# StrobeV3.net
KiCad netlist of a schematic drawn in EAGLE
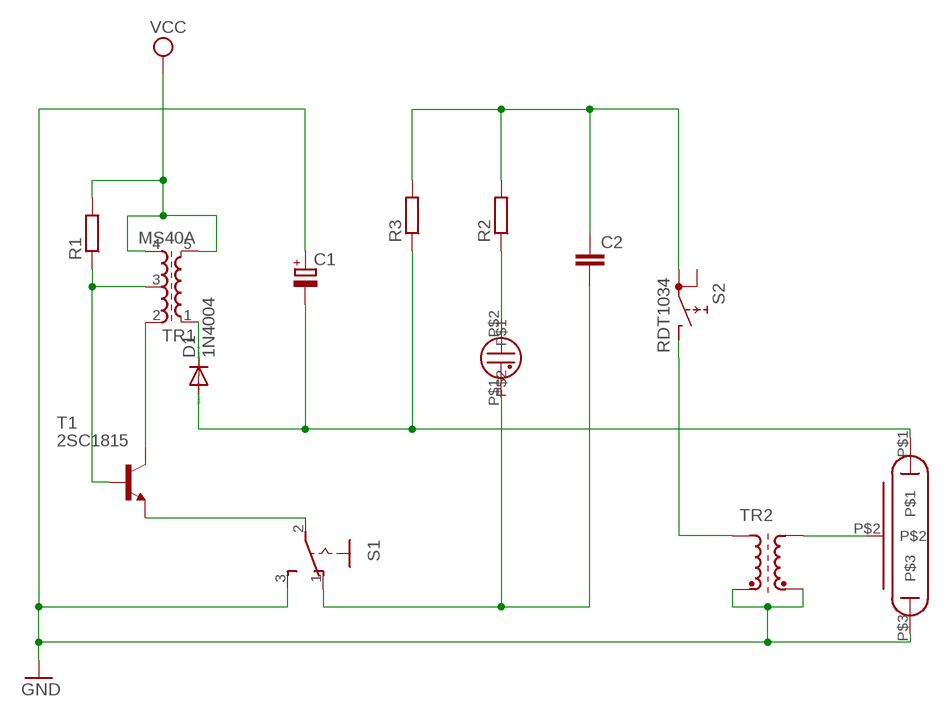
[diagram p0: schematic, sheet 1]

(export (version "E")
  (design (tool "Eeschema 10.0.6"))
  (components
    (comp (ref "C1")
      (value "CPOL-EU140CLH-0810")
      (footprint "eagle-import:140CLH-0810")
      (libsource (lib "eagle-import") (part "CPOL-EU140CLH-0810"))
    )
    (comp (ref "C2")
      (value "C-EU150-054X183")
      (footprint "eagle-import:C150-054X183")
      (libsource (lib "eagle-import") (part "C-EU150-054X183"))
    )
    (comp (ref "D1")
      (value "1N4004")
      (footprint "eagle-import:DO41-10")
      (libsource (lib "eagle-import") (part "1N4004"))
    )
    (comp (ref "R1")
      (value "R-EU_0204/2V")
      (footprint "eagle-import:0204V")
      (libsource (lib "eagle-import") (part "R-EU_0204/2V"))
    )
    (comp (ref "R2")
      (value "R-EU_0204/2V")
      (footprint "eagle-import:0204V")
      (libsource (lib "eagle-import") (part "R-EU_0204/2V"))
    )
    (comp (ref "R3")
      (value "R-EU_0204/2V")
      (footprint "eagle-import:0204V")
      (libsource (lib "eagle-import") (part "R-EU_0204/2V"))
    )
    (comp (ref "S1")
      (value "255SB")
      (footprint "eagle-import:255SB")
      (libsource (lib "eagle-import") (part "255SB"))
    )
    (comp (ref "S2")
      (value "RDT1034")
      (footprint "eagle-import:RDT1034")
      (libsource (lib "eagle-import") (part "RDT1034"))
    )
    (comp (ref "T1")
      (value "2SC1815")
      (footprint "eagle-import:TO92-ECB")
      (libsource (lib "eagle-import") (part "2SC1815"))
    )
    (comp (ref "TR1")
      (value "MS40A")
      (footprint "eagle-import:MS40")
      (libsource (lib "eagle-import") (part "MS40A"))
    )
    (comp (ref "TR2")
      (value "SM-T4")
      (footprint "eagle-import:SM-T4")
      (libsource (lib "eagle-import") (part "SM-T4"))
    )
    (comp (ref "U$1")
      (value "XENON")
      (footprint "eagle-import:XENON")
      (libsource (lib "eagle-import") (part "XENON"))
    )
    (comp (ref "U$2")
      (value "NEON")
      (footprint "eagle-import:NEON")
      (libsource (lib "eagle-import") (part "NEON"))
    )
  )
  (nets
    (net (code "1") (name "GND") (class "Default")
      (node (ref "C1") (pin "+") (pinfunction "+_+") (pintype "passive"))
      (node (ref "S1") (pin "3") (pinfunction "S_3") (pintype "passive"))
      (node (ref "TR2") (pin "2") (pinfunction "E1_2") (pintype "passive"))
      (node (ref "TR2") (pin "4") (pinfunction "E2_4") (pintype "passive"))
      (node (ref "U$1") (pin "P$3") (pinfunction "P$3_P$3") (pintype "bidirectional"))
    )
    (net (code "2") (name "Net-(C1-Pad-)") (class "Default")
      (node (ref "C1") (pin "-") (pinfunction "-_-") (pintype "passive"))
      (node (ref "D1") (pin "A") (pinfunction "A_A") (pintype "passive"))
      (node (ref "R3") (pin "1") (pinfunction "1_1") (pintype "passive"))
      (node (ref "U$1") (pin "P$1") (pinfunction "P$1_P$1") (pintype "bidirectional"))
    )
    (net (code "3") (name "Net-(C2-Pad1)") (class "Default")
      (node (ref "C2") (pin "1") (pinfunction "1_1") (pintype "passive"))
      (node (ref "R2") (pin "2") (pinfunction "2_2") (pintype "passive"))
      (node (ref "R3") (pin "2") (pinfunction "2_2") (pintype "passive"))
      (node (ref "S2") (pin "A1") (pinfunction "A1_A1") (pintype "passive"))
    )
    (net (code "4") (name "Net-(D1-PadC)") (class "Default")
      (node (ref "D1") (pin "C") (pinfunction "C_C") (pintype "passive"))
      (node (ref "TR1") (pin "1") (pinfunction "1_1") (pintype "passive"))
    )
    (net (code "5") (name "Net-(R1-Pad1)") (class "Default")
      (node (ref "R1") (pin "1") (pinfunction "1_1") (pintype "passive"))
      (node (ref "T1") (pin "B") (pinfunction "B_B") (pintype "passive"))
      (node (ref "TR1") (pin "3") (pinfunction "3_3") (pintype "passive"))
    )
    (net (code "6") (name "Net-(R2-Pad1)") (class "Default")
      (node (ref "R2") (pin "1") (pinfunction "1_1") (pintype "passive"))
      (node (ref "U$2") (pin "P$2") (pinfunction "P$2_P$2") (pintype "bidirectional"))
    )
    (net (code "7") (name "Net-(S1-O)") (class "Default")
      (node (ref "C2") (pin "2") (pinfunction "2_2") (pintype "passive"))
      (node (ref "S1") (pin "1") (pinfunction "O_1") (pintype "passive"))
      (node (ref "U$2") (pin "P$1") (pinfunction "P$1_P$1") (pintype "bidirectional"))
    )
    (net (code "8") (name "Net-(S1-P)") (class "Default")
      (node (ref "S1") (pin "2") (pinfunction "P_2") (pintype "passive"))
      (node (ref "T1") (pin "E") (pinfunction "E_E") (pintype "passive"))
    )
    (net (code "9") (name "Net-(T1-PadC)") (class "Default")
      (node (ref "T1") (pin "C") (pinfunction "C_C") (pintype "passive"))
      (node (ref "TR1") (pin "2") (pinfunction "2_2") (pintype "passive"))
    )
    (net (code "10") (name "Net-(TR2-A1)") (class "Default")
      (node (ref "S2") (pin "B") (pinfunction "B_B") (pintype "passive"))
      (node (ref "TR2") (pin "1") (pinfunction "A1_1") (pintype "passive"))
    )
    (net (code "11") (name "Net-(TR2-A2)") (class "Default")
      (node (ref "TR2") (pin "5") (pinfunction "A2_5") (pintype "passive"))
      (node (ref "U$1") (pin "P$2") (pinfunction "P$2_P$2") (pintype "bidirectional"))
    )
    (net (code "12") (name "VCC") (class "Default")
      (node (ref "R1") (pin "2") (pinfunction "2_2") (pintype "passive"))
      (node (ref "TR1") (pin "4") (pinfunction "4_4") (pintype "passive"))
      (node (ref "TR1") (pin "5") (pinfunction "5_5") (pintype "passive"))
    )
    (net (code "13") (name "unconnected-(S2-PadA)") (class "Default")
      (node (ref "S2") (pin "A") (pinfunction "A_A") (pintype "passive"))
    )
  )
)
